# electromagnetic.net
KiCad netlist of a schematic drawn in Altium Designer
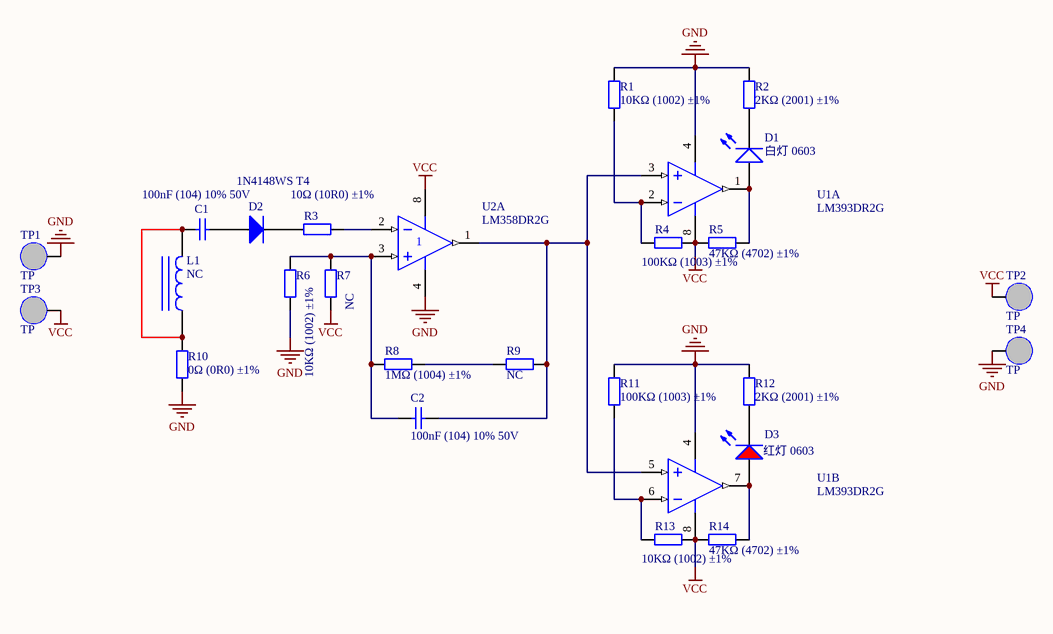
[diagram p0: electromagnetic.SchDoc]

(export (version "E")
  (design (tool "Eeschema 10.0.6"))
  (components
    (comp (ref "C1")
      (value "100nF (104) 10% 50V")
      (footprint "0603_C")
      (description "贴片电容")
      (libsource (lib "Miscellaneous Devices LC") (part "0603 100nF (104) 10% 50V"))
    )
    (comp (ref "C2")
      (value "100nF (104) 10% 50V")
      (footprint "0603_C")
      (description "贴片电容")
      (libsource (lib "Miscellaneous Devices LC") (part "0603 100nF (104) 10% 50V"))
    )
    (comp (ref "D1")
      (value "白灯 0603")
      (footprint "0603_LED_S1")
      (description "发光二极管")
      (libsource (lib "Miscellaneous Devices LC") (part "0603 白灯"))
    )
    (comp (ref "D2")
      (value "1N4148WS T4")
      (footprint "SOD-323")
      (description "二极管")
      (libsource (lib "Miscellaneous Devices LC") (part "SOD-323 1N4148WS T4"))
    )
    (comp (ref "D3")
      (value "红灯 0603")
      (footprint "0603_LED_S1")
      (description "发光二极管")
      (libsource (lib "Miscellaneous Devices LC") (part "0603 红灯"))
    )
    (comp (ref "L1")
      (value "NC")
      (footprint "0603_L")
      (description "贴片电感")
      (libsource (lib "Miscellaneous Devices LC") (part "0603 47nH"))
    )
    (comp (ref "R1")
      (value "10KΩ (1002) ±1%")
      (footprint "0603_R")
      (description "贴片电阻")
      (libsource (lib "Miscellaneous Devices LC") (part "0603 10KΩ (1002) 1%"))
    )
    (comp (ref "R2")
      (value "2KΩ (2001) ±1%")
      (footprint "0603_R")
      (description "贴片电阻")
      (libsource (lib "Miscellaneous Devices LC") (part "0603 2KΩ (2001) 1%"))
    )
    (comp (ref "R3")
      (value "10Ω (10R0) ±1%")
      (footprint "0603_R")
      (description "贴片电阻")
      (libsource (lib "Miscellaneous Devices LC") (part "0603 10Ω (10R0) 1%"))
    )
    (comp (ref "R4")
      (value "100KΩ (1003) ±1%")
      (footprint "0603_R")
      (description "贴片电阻")
      (libsource (lib "Miscellaneous Devices LC") (part "0603 100KΩ (1003) 1%"))
    )
    (comp (ref "R5")
      (value "47KΩ (4702) ±1%")
      (footprint "0603_R")
      (description "贴片电阻")
      (libsource (lib "Miscellaneous Devices LC") (part "0603 47KΩ (4702) 1%"))
    )
    (comp (ref "R6")
      (value "10KΩ (1002) ±1%")
      (footprint "0603_R")
      (description "贴片电阻")
      (libsource (lib "Miscellaneous Devices LC") (part "0603 10KΩ (1002) 1%"))
    )
    (comp (ref "R7")
      (value "NC")
      (footprint "0603_R")
      (description "贴片电阻")
      (libsource (lib "Miscellaneous Devices LC") (part "0603 1KΩ (1001) 1%"))
    )
    (comp (ref "R8")
      (value "1MΩ (1004) ±1%")
      (footprint "0603_R")
      (description "贴片电阻")
      (libsource (lib "Miscellaneous Devices LC") (part "0603 1MΩ (1004) 1%"))
    )
    (comp (ref "R9")
      (value "NC")
      (footprint "0603_R")
      (description "贴片电阻")
      (libsource (lib "Miscellaneous Devices LC") (part "0603 1MΩ (1004) 1%"))
    )
    (comp (ref "R10")
      (value "0Ω (0R0) ±1%")
      (footprint "0603_R")
      (description "贴片电阻")
      (libsource (lib "Miscellaneous Devices LC") (part "0603 0Ω (0R0) 1%"))
    )
    (comp (ref "R11")
      (value "100KΩ (1003) ±1%")
      (footprint "0603_R")
      (description "贴片电阻")
      (libsource (lib "") (part "0603 100KΩ (1003) 1%_1"))
    )
    (comp (ref "R12")
      (value "2KΩ (2001) ±1%")
      (footprint "0603_R")
      (description "贴片电阻")
      (libsource (lib "Miscellaneous Devices LC") (part "0603 2KΩ (2001) 1%"))
    )
    (comp (ref "R13")
      (value "10KΩ (1002) ±1%")
      (footprint "0603_R")
      (description "贴片电阻")
      (libsource (lib "") (part "0603 10KΩ (1002) 1%_1"))
    )
    (comp (ref "R14")
      (value "47KΩ (4702) ±1%")
      (footprint "0603_R")
      (description "贴片电阻")
      (libsource (lib "Miscellaneous Devices LC") (part "0603 47KΩ (4702) 1%"))
    )
    (comp (ref "TP1") (value "TP") (footprint "TP") (libsource (lib "mylib") (part "TP")))
    (comp (ref "TP2") (value "TP") (footprint "TP") (libsource (lib "mylib") (part "TP")))
    (comp (ref "TP3") (value "TP") (footprint "TP") (libsource (lib "mylib") (part "TP")))
    (comp (ref "TP4") (value "TP") (footprint "TP") (libsource (lib "mylib") (part "TP")))
    (comp (ref "U1")
      (value "LM393DR2G")
      (footprint "SOIC-8_150mil")
      (description "电压比较器")
      (libsource (lib "Miscellaneous Devices LC") (part "LM393DR2G_[C7955]"))
    )
    (comp (ref "U2")
      (value "LM358DR2G")
      (footprint "SOIC-8_150mil")
      (description "通用运放")
      (libsource (lib "Miscellaneous Devices LC") (part "LM358DR2G_[C7950]"))
    )
  )
  (nets
    (net (code "1") (name "GND") (class "Default")
      (node (ref "R1") (pin "2") (pinfunction "2_2") (pintype "passive"))
      (node (ref "R10") (pin "1") (pinfunction "1_1") (pintype "passive"))
      (node (ref "R11") (pin "2") (pinfunction "2_2") (pintype "passive"))
      (node (ref "R12") (pin "2") (pinfunction "2_2") (pintype "passive"))
      (node (ref "R2") (pin "2") (pinfunction "2_2") (pintype "passive"))
      (node (ref "R6") (pin "1") (pinfunction "1_1") (pintype "passive"))
      (node (ref "TP1") (pin "1") (pinfunction "1_1") (pintype "passive"))
      (node (ref "TP4") (pin "1") (pinfunction "1_1") (pintype "passive"))
      (node (ref "U1") (pin "4") (pinfunction "GND_4") (pintype "power_in"))
      (node (ref "U2") (pin "4") (pinfunction "V-_4") (pintype "power_in"))
    )
    (net (code "2") (name "Net-(C1-Pad1)") (class "Default")
      (node (ref "C1") (pin "1") (pinfunction "1_1") (pintype "passive"))
      (node (ref "L1") (pin "1") (pinfunction "1_1") (pintype "passive"))
      (node (ref "L1") (pin "2") (pinfunction "2_2") (pintype "passive"))
      (node (ref "R10") (pin "2") (pinfunction "2_2") (pintype "passive"))
    )
    (net (code "3") (name "Net-(D1-PadK)") (class "Default")
      (node (ref "D1") (pin "K") (pinfunction "K_K") (pintype "passive"))
      (node (ref "R2") (pin "1") (pinfunction "1_1") (pintype "passive"))
    )
    (net (code "4") (name "Net-(D2-A)") (class "Default")
      (node (ref "C1") (pin "2") (pinfunction "2_2") (pintype "passive"))
      (node (ref "D2") (pin "1") (pinfunction "A_1") (pintype "passive"))
    )
    (net (code "5") (name "Net-(D2-K)") (class "Default")
      (node (ref "D2") (pin "2") (pinfunction "K_2") (pintype "passive"))
      (node (ref "R3") (pin "1") (pinfunction "1_1") (pintype "passive"))
    )
    (net (code "6") (name "Net-(D3-PadK)") (class "Default")
      (node (ref "D3") (pin "K") (pinfunction "K_K") (pintype "passive"))
      (node (ref "R12") (pin "1") (pinfunction "1_1") (pintype "passive"))
    )
    (net (code "7") (name "Net-(R8-Pad2)") (class "Default")
      (node (ref "R8") (pin "2") (pinfunction "2_2") (pintype "passive"))
      (node (ref "R9") (pin "1") (pinfunction "1_1") (pintype "passive"))
    )
    (net (code "8") (name "Net-(U1A-IN+)") (class "Default")
      (node (ref "C2") (pin "2") (pinfunction "2_2") (pintype "passive"))
      (node (ref "R9") (pin "2") (pinfunction "2_2") (pintype "passive"))
      (node (ref "U1") (pin "3") (pinfunction "IN+_3") (pintype "input"))
      (node (ref "U1") (pin "5") (pinfunction "IN+_5") (pintype "input"))
      (node (ref "U2") (pin "1") (pinfunction "OUT_1") (pintype "output"))
    )
    (net (code "9") (name "Net-(U1A-IN-)") (class "Default")
      (node (ref "R1") (pin "1") (pinfunction "1_1") (pintype "passive"))
      (node (ref "R4") (pin "1") (pinfunction "1_1") (pintype "passive"))
      (node (ref "U1") (pin "2") (pinfunction "IN-_2") (pintype "input"))
    )
    (net (code "10") (name "Net-(U1A-OUT)") (class "Default")
      (node (ref "D1") (pin "A") (pinfunction "A_A") (pintype "passive"))
      (node (ref "R5") (pin "2") (pinfunction "2_2") (pintype "passive"))
      (node (ref "U1") (pin "1") (pinfunction "OUT_1") (pintype "output"))
    )
    (net (code "11") (name "Net-(U1B-IN-)") (class "Default")
      (node (ref "R11") (pin "1") (pinfunction "1_1") (pintype "passive"))
      (node (ref "R13") (pin "2") (pinfunction "2_2") (pintype "passive"))
      (node (ref "U1") (pin "6") (pinfunction "IN-_6") (pintype "input"))
    )
    (net (code "12") (name "Net-(U1B-OUT)") (class "Default")
      (node (ref "D3") (pin "A") (pinfunction "A_A") (pintype "passive"))
      (node (ref "R14") (pin "2") (pinfunction "2_2") (pintype "passive"))
      (node (ref "U1") (pin "7") (pinfunction "OUT_7") (pintype "output"))
    )
    (net (code "13") (name "Net-(U2A-IN+)") (class "Default")
      (node (ref "C2") (pin "1") (pinfunction "1_1") (pintype "passive"))
      (node (ref "R6") (pin "2") (pinfunction "2_2") (pintype "passive"))
      (node (ref "R7") (pin "2") (pinfunction "2_2") (pintype "passive"))
      (node (ref "R8") (pin "1") (pinfunction "1_1") (pintype "passive"))
      (node (ref "U2") (pin "3") (pinfunction "IN+_3") (pintype "input"))
    )
    (net (code "14") (name "Net-(U2A-IN-)") (class "Default")
      (node (ref "R3") (pin "2") (pinfunction "2_2") (pintype "passive"))
      (node (ref "U2") (pin "2") (pinfunction "IN-_2") (pintype "input"))
    )
    (net (code "15") (name "VCC") (class "Default")
      (node (ref "R13") (pin "1") (pinfunction "1_1") (pintype "passive"))
      (node (ref "R14") (pin "1") (pinfunction "1_1") (pintype "passive"))
      (node (ref "R4") (pin "2") (pinfunction "2_2") (pintype "passive"))
      (node (ref "R5") (pin "1") (pinfunction "1_1") (pintype "passive"))
      (node (ref "R7") (pin "1") (pinfunction "1_1") (pintype "passive"))
      (node (ref "TP2") (pin "1") (pinfunction "1_1") (pintype "passive"))
      (node (ref "TP3") (pin "1") (pinfunction "1_1") (pintype "passive"))
      (node (ref "U1") (pin "8") (pinfunction "V+_8") (pintype "power_in"))
      (node (ref "U2") (pin "8") (pinfunction "V+_8") (pintype "power_in"))
    )
  )
)
